# LCD_Interface_Board_V1_0.net
KiCad netlist of a schematic drawn in EAGLE
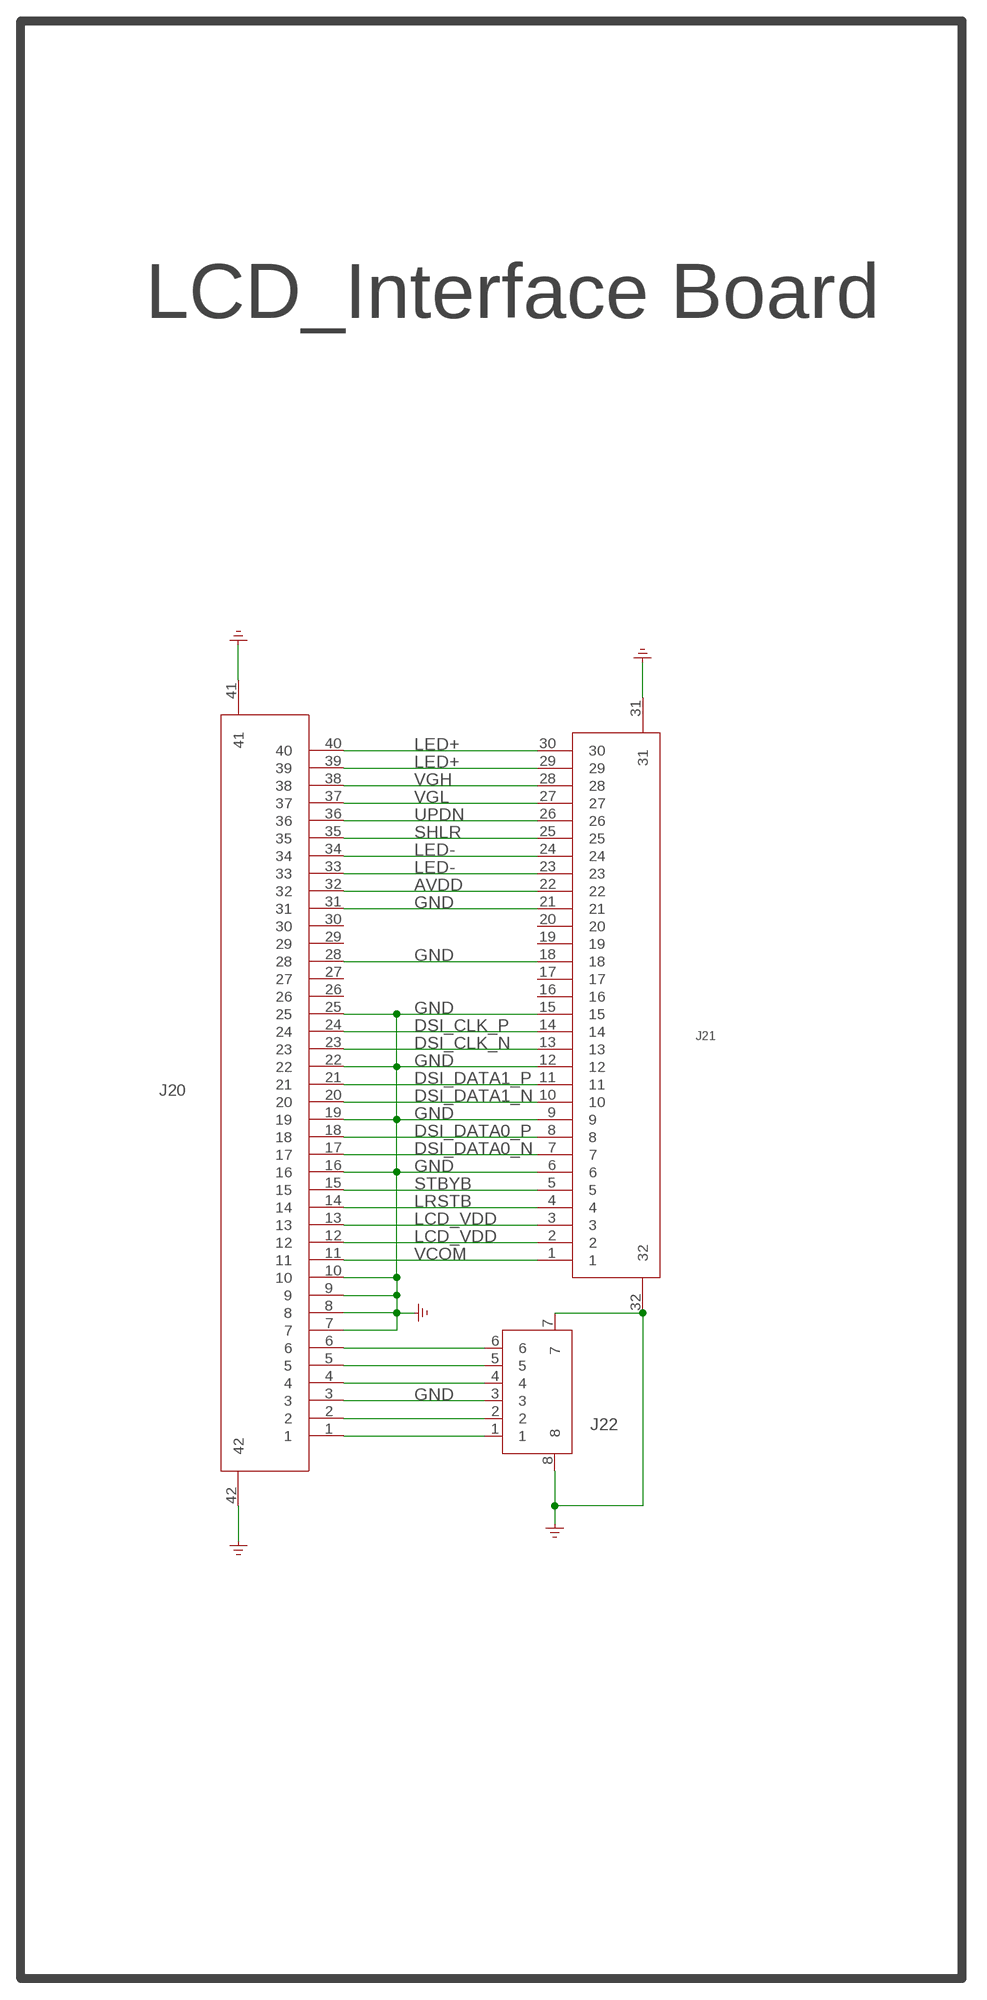
[diagram p0: schematic, sheet 1]

(export (version "E")
  (design (tool "Eeschema 10.0.6"))
  (components
    (comp (ref "J20")
      (value "C19273935_40P_0.5MM_下接_HC-FPC-0.5-40P-FH20")
      (footprint "eagle-import:C19273935_40P_0.5MM_下接_HC-FPC-0.5-40P-FH20")
      (libsource (lib "eagle-import") (part "C19273935_40P_0.5MM_下接_HC-FPC-0.5-40P-FH20"))
    )
    (comp (ref "J21")
      (value "C23398852_30P_0.5MM_下接_FC-05A30P11H20")
      (footprint "eagle-import:C23398852_30P_0.5MM_下接_FC-05A30P11H20")
      (libsource (lib "eagle-import") (part "C23398852_30P_0.5MM_下接_FC-05A30P11H20"))
    )
    (comp (ref "J22")
      (value "C2856814_6P_0.5MM_下接_FPC-05F-6PH15")
      (footprint "eagle-import:C2856814_6P_0.5MM_下接_FPC-05F-6PH15")
      (libsource (lib "eagle-import") (part "C2856814_6P_0.5MM_下接_FPC-05F-6PH15"))
    )
  )
  (nets
    (net (code "1") (name "/AVDD") (class "Default")
      (node (ref "J20") (pin "32") (pinfunction "32_32") (pintype "bidirectional"))
      (node (ref "J21") (pin "22") (pinfunction "22_22") (pintype "bidirectional"))
    )
    (net (code "2") (name "/DSI_CLK_N") (class "Default")
      (node (ref "J20") (pin "23") (pinfunction "23_23") (pintype "bidirectional"))
      (node (ref "J21") (pin "13") (pinfunction "13_13") (pintype "bidirectional"))
    )
    (net (code "3") (name "/DSI_CLK_P") (class "Default")
      (node (ref "J20") (pin "24") (pinfunction "24_24") (pintype "bidirectional"))
      (node (ref "J21") (pin "14") (pinfunction "14_14") (pintype "bidirectional"))
    )
    (net (code "4") (name "/DSI_DATA0_N") (class "Default")
      (node (ref "J20") (pin "17") (pinfunction "17_17") (pintype "bidirectional"))
      (node (ref "J21") (pin "7") (pinfunction "7_7") (pintype "bidirectional"))
    )
    (net (code "5") (name "/DSI_DATA0_P") (class "Default")
      (node (ref "J20") (pin "18") (pinfunction "18_18") (pintype "bidirectional"))
      (node (ref "J21") (pin "8") (pinfunction "8_8") (pintype "bidirectional"))
    )
    (net (code "6") (name "/DSI_DATA1_N") (class "Default")
      (node (ref "J20") (pin "20") (pinfunction "20_20") (pintype "bidirectional"))
      (node (ref "J21") (pin "10") (pinfunction "10_10") (pintype "bidirectional"))
    )
    (net (code "7") (name "/DSI_DATA1_P") (class "Default")
      (node (ref "J20") (pin "21") (pinfunction "21_21") (pintype "bidirectional"))
      (node (ref "J21") (pin "11") (pinfunction "11_11") (pintype "bidirectional"))
    )
    (net (code "8") (name "/LCD_VDD") (class "Default")
      (node (ref "J20") (pin "12") (pinfunction "12_12") (pintype "bidirectional"))
      (node (ref "J20") (pin "13") (pinfunction "13_13") (pintype "bidirectional"))
      (node (ref "J21") (pin "2") (pinfunction "2_2") (pintype "bidirectional"))
      (node (ref "J21") (pin "3") (pinfunction "3_3") (pintype "bidirectional"))
    )
    (net (code "9") (name "/LED+") (class "Default")
      (node (ref "J20") (pin "39") (pinfunction "39_39") (pintype "bidirectional"))
      (node (ref "J20") (pin "40") (pinfunction "40_40") (pintype "bidirectional"))
      (node (ref "J21") (pin "29") (pinfunction "29_29") (pintype "bidirectional"))
      (node (ref "J21") (pin "30") (pinfunction "30_30") (pintype "bidirectional"))
    )
    (net (code "10") (name "/LED-") (class "Default")
      (node (ref "J20") (pin "33") (pinfunction "33_33") (pintype "bidirectional"))
      (node (ref "J20") (pin "34") (pinfunction "34_34") (pintype "bidirectional"))
      (node (ref "J21") (pin "23") (pinfunction "23_23") (pintype "bidirectional"))
      (node (ref "J21") (pin "24") (pinfunction "24_24") (pintype "bidirectional"))
    )
    (net (code "11") (name "/LRSTB") (class "Default")
      (node (ref "J20") (pin "14") (pinfunction "14_14") (pintype "bidirectional"))
      (node (ref "J21") (pin "4") (pinfunction "4_4") (pintype "bidirectional"))
    )
    (net (code "12") (name "/SHLR") (class "Default")
      (node (ref "J20") (pin "35") (pinfunction "35_35") (pintype "bidirectional"))
      (node (ref "J21") (pin "25") (pinfunction "25_25") (pintype "bidirectional"))
    )
    (net (code "13") (name "/STBYB") (class "Default")
      (node (ref "J20") (pin "15") (pinfunction "15_15") (pintype "bidirectional"))
      (node (ref "J21") (pin "5") (pinfunction "5_5") (pintype "bidirectional"))
    )
    (net (code "14") (name "/UPDN") (class "Default")
      (node (ref "J20") (pin "36") (pinfunction "36_36") (pintype "bidirectional"))
      (node (ref "J21") (pin "26") (pinfunction "26_26") (pintype "bidirectional"))
    )
    (net (code "15") (name "/VCOM") (class "Default")
      (node (ref "J20") (pin "11") (pinfunction "11_11") (pintype "bidirectional"))
      (node (ref "J21") (pin "1") (pinfunction "1_1") (pintype "bidirectional"))
    )
    (net (code "16") (name "/VGH") (class "Default")
      (node (ref "J20") (pin "38") (pinfunction "38_38") (pintype "bidirectional"))
      (node (ref "J21") (pin "28") (pinfunction "28_28") (pintype "bidirectional"))
    )
    (net (code "17") (name "/VGL") (class "Default")
      (node (ref "J20") (pin "37") (pinfunction "37_37") (pintype "bidirectional"))
      (node (ref "J21") (pin "27") (pinfunction "27_27") (pintype "bidirectional"))
    )
    (net (code "18") (name "Net-(J20-Pad1)") (class "Default")
      (node (ref "J20") (pin "1") (pinfunction "1_1") (pintype "bidirectional"))
      (node (ref "J22") (pin "1") (pinfunction "1_1") (pintype "bidirectional"))
    )
    (net (code "19") (name "Net-(J20-Pad2)") (class "Default")
      (node (ref "J20") (pin "2") (pinfunction "2_2") (pintype "bidirectional"))
      (node (ref "J22") (pin "2") (pinfunction "2_2") (pintype "bidirectional"))
    )
    (net (code "20") (name "Net-(J20-Pad4)") (class "Default")
      (node (ref "J20") (pin "4") (pinfunction "4_4") (pintype "bidirectional"))
      (node (ref "J22") (pin "4") (pinfunction "4_4") (pintype "bidirectional"))
    )
    (net (code "21") (name "Net-(J20-Pad5)") (class "Default")
      (node (ref "J20") (pin "5") (pinfunction "5_5") (pintype "bidirectional"))
      (node (ref "J22") (pin "5") (pinfunction "5_5") (pintype "bidirectional"))
    )
    (net (code "22") (name "Net-(J20-Pad6)") (class "Default")
      (node (ref "J20") (pin "6") (pinfunction "6_6") (pintype "bidirectional"))
      (node (ref "J22") (pin "6") (pinfunction "6_6") (pintype "bidirectional"))
    )
    (net (code "23") (name "POWER_GND") (class "Default")
      (node (ref "J20") (pin "10") (pinfunction "10_10") (pintype "bidirectional"))
      (node (ref "J20") (pin "16") (pinfunction "16_16") (pintype "bidirectional"))
      (node (ref "J20") (pin "19") (pinfunction "19_19") (pintype "bidirectional"))
      (node (ref "J20") (pin "22") (pinfunction "22_22") (pintype "bidirectional"))
      (node (ref "J20") (pin "25") (pinfunction "25_25") (pintype "bidirectional"))
      (node (ref "J20") (pin "28") (pinfunction "28_28") (pintype "bidirectional"))
      (node (ref "J20") (pin "3") (pinfunction "3_3") (pintype "bidirectional"))
      (node (ref "J20") (pin "31") (pinfunction "31_31") (pintype "bidirectional"))
      (node (ref "J20") (pin "41") (pinfunction "41_41") (pintype "bidirectional"))
      (node (ref "J20") (pin "42") (pinfunction "42_42") (pintype "bidirectional"))
      (node (ref "J20") (pin "7") (pinfunction "7_7") (pintype "bidirectional"))
      (node (ref "J20") (pin "8") (pinfunction "8_8") (pintype "bidirectional"))
      (node (ref "J20") (pin "9") (pinfunction "9_9") (pintype "bidirectional"))
      (node (ref "J21") (pin "12") (pinfunction "12_12") (pintype "bidirectional"))
      (node (ref "J21") (pin "15") (pinfunction "15_15") (pintype "bidirectional"))
      (node (ref "J21") (pin "18") (pinfunction "18_18") (pintype "bidirectional"))
      (node (ref "J21") (pin "21") (pinfunction "21_21") (pintype "bidirectional"))
      (node (ref "J21") (pin "31") (pinfunction "31_31") (pintype "bidirectional"))
      (node (ref "J21") (pin "32") (pinfunction "32_32") (pintype "bidirectional"))
      (node (ref "J21") (pin "6") (pinfunction "6_6") (pintype "bidirectional"))
      (node (ref "J21") (pin "9") (pinfunction "9_9") (pintype "bidirectional"))
      (node (ref "J22") (pin "3") (pinfunction "3_3") (pintype "bidirectional"))
      (node (ref "J22") (pin "7") (pinfunction "7_7") (pintype "bidirectional"))
      (node (ref "J22") (pin "8") (pinfunction "8_8") (pintype "bidirectional"))
    )
    (net (code "24") (name "unconnected-(J20-Pad26)") (class "Default")
      (node (ref "J20") (pin "26") (pinfunction "26_26") (pintype "bidirectional"))
    )
    (net (code "25") (name "unconnected-(J20-Pad27)") (class "Default")
      (node (ref "J20") (pin "27") (pinfunction "27_27") (pintype "bidirectional"))
    )
    (net (code "26") (name "unconnected-(J20-Pad29)") (class "Default")
      (node (ref "J20") (pin "29") (pinfunction "29_29") (pintype "bidirectional"))
    )
    (net (code "27") (name "unconnected-(J20-Pad30)") (class "Default")
      (node (ref "J20") (pin "30") (pinfunction "30_30") (pintype "bidirectional"))
    )
    (net (code "28") (name "unconnected-(J21-Pad16)") (class "Default")
      (node (ref "J21") (pin "16") (pinfunction "16_16") (pintype "bidirectional"))
    )
    (net (code "29") (name "unconnected-(J21-Pad17)") (class "Default")
      (node (ref "J21") (pin "17") (pinfunction "17_17") (pintype "bidirectional"))
    )
    (net (code "30") (name "unconnected-(J21-Pad19)") (class "Default")
      (node (ref "J21") (pin "19") (pinfunction "19_19") (pintype "bidirectional"))
    )
    (net (code "31") (name "unconnected-(J21-Pad20)") (class "Default")
      (node (ref "J21") (pin "20") (pinfunction "20_20") (pintype "bidirectional"))
    )
  )
)
